# GPT_Schematic.net
KiCad netlist of a schematic drawn in Altium Designer
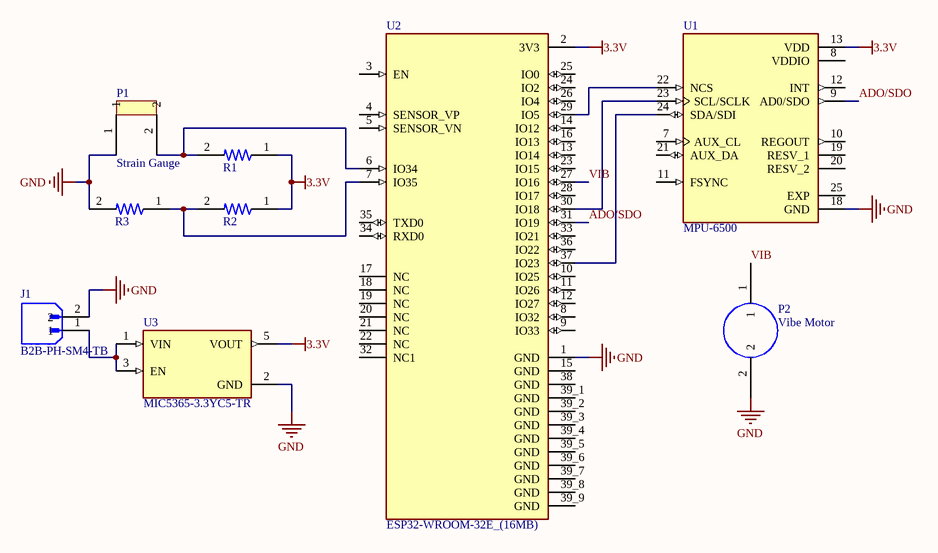
[diagram p0: GPT_Schematic.SchDoc]

(export (version "E")
  (design (tool "Eeschema 10.0.6"))
  (components
    (comp (ref "J1")
      (value "B2B-PH-SM4-TB")
      (footprint "JST_B2B-PH-SM4-TB")
      (description "Connector Header Surface Mount 2 position 0.079 (2.00mm)")
      (fields (field (name "MF") "JST"))
      (libsource (lib "B2B-PH-SM4-TB") (part "B2B-PH-SM4-TB"))
    )
    (comp (ref "P1")
      (value "Strain Gauge")
      (footprint "Strain Gauge")
      (libsource (lib "GPT_PCB") (part "Strain Gauge"))
    )
    (comp (ref "P2")
      (value "Vibe Motor")
      (footprint "Vibe Motor")
      (libsource (lib "GPT_PCB") (part "Vibe Motor"))
    )
    (comp (ref "R1")
      (value "RC0603FR-07100RL")
      (footprint "RESC1607X60N")
      (description "RES SMT 100R 1% 0603 T/R PICK#92931")
      (libsource (lib "RC0603FR-07100RL") (part "RC0603FR-07100RL"))
    )
    (comp (ref "R2")
      (value "RC0603FR-07100RL")
      (footprint "RESC1607X60N")
      (description "RES SMT 100R 1% 0603 T/R PICK#92931")
      (libsource (lib "RC0603FR-07100RL") (part "RC0603FR-07100RL"))
    )
    (comp (ref "R3")
      (value "RC0603FR-07100RL")
      (footprint "RESC1607X60N")
      (description "RES SMT 100R 1% 0603 T/R PICK#92931")
      (libsource (lib "RC0603FR-07100RL") (part "RC0603FR-07100RL"))
    )
    (comp (ref "U1")
      (value "MPU-6500")
      (footprint "QFN40P300X300X95-25N")
      (description "Accelerometer, Gyroscope, 6 Axis Sensor IÂ²C, SPI Output")
      (fields (field (name "MF") "TDK InvenSense"))
      (libsource (lib "MPU-6500") (part "MPU-6500"))
    )
    (comp (ref "U2")
      (value "ESP32-WROOM-32E_(16MB)")
      (footprint "XCVR_ESP32-WROOM-32E_(16MB)")
      (fields (field (name "MP") "ESP32-WROOM-32E (16MB)") (field (name "MF") "Espressif Systems"))
      (libsource (lib "ESP32-WROOM-32E__16MB_") (part "ESP32-WROOM-32E_(16MB)"))
    )
    (comp (ref "U3")
      (value "MIC5365-3.3YC5-TR")
      (footprint "SOT65P210X110-5N")
      (description "Linear Voltage Regulator IC 1 Output 150mA SC-70-5")
      (libsource (lib "MIC5365-3.3YC5-TR") (part "MIC5365-3.3YC5-TR"))
    )
  )
  (nets
    (net (code "1") (name "/ADO{slash}SDO") (class "Default")
      (node (ref "U1") (pin "9") (pinfunction "AD0/SDO_9") (pintype "output"))
      (node (ref "U2") (pin "31") (pinfunction "IO19_31") (pintype "bidirectional"))
    )
    (net (code "2") (name "/VIB") (class "Default")
      (node (ref "P2") (pin "1") (pinfunction "1_1") (pintype "passive"))
      (node (ref "U2") (pin "27") (pinfunction "IO16_27") (pintype "bidirectional"))
    )
    (net (code "3") (name "3.3V") (class "Default")
      (node (ref "R1") (pin "1") (pinfunction "1_1") (pintype "passive"))
      (node (ref "R2") (pin "1") (pinfunction "1_1") (pintype "passive"))
      (node (ref "U1") (pin "13") (pinfunction "VDD_13") (pintype "power_in"))
      (node (ref "U2") (pin "2") (pinfunction "3V3_2") (pintype "power_in"))
      (node (ref "U3") (pin "5") (pinfunction "VOUT_5") (pintype "output"))
    )
    (net (code "4") (name "GND") (class "Default")
      (node (ref "J1") (pin "2") (pinfunction "2_2") (pintype "passive"))
      (node (ref "P1") (pin "1") (pinfunction "1_1") (pintype "passive"))
      (node (ref "P2") (pin "2") (pinfunction "2_2") (pintype "passive"))
      (node (ref "R3") (pin "2") (pinfunction "2_2") (pintype "passive"))
      (node (ref "U1") (pin "18") (pinfunction "GND_18") (pintype "power_in"))
      (node (ref "U2") (pin "1") (pinfunction "GND_1") (pintype "power_in"))
      (node (ref "U3") (pin "2") (pinfunction "GND_2") (pintype "power_in"))
    )
    (net (code "5") (name "Net-(U1-NCS)") (class "Default")
      (node (ref "U1") (pin "22") (pinfunction "NCS_22") (pintype "input"))
      (node (ref "U2") (pin "29") (pinfunction "IO5_29") (pintype "bidirectional"))
    )
    (net (code "6") (name "Net-(U1-SCL{slash}SCLK)") (class "Default")
      (node (ref "U1") (pin "23") (pinfunction "SCL/SCLK_23") (pintype "input"))
      (node (ref "U2") (pin "30") (pinfunction "IO18_30") (pintype "bidirectional"))
    )
    (net (code "7") (name "Net-(U1-SDA{slash}SDI)") (class "Default")
      (node (ref "U1") (pin "24") (pinfunction "SDA/SDI_24") (pintype "bidirectional"))
      (node (ref "U2") (pin "37") (pinfunction "IO23_37") (pintype "bidirectional"))
    )
    (net (code "8") (name "Net-(U2-IO34)") (class "Default")
      (node (ref "P1") (pin "2") (pinfunction "2_2") (pintype "passive"))
      (node (ref "R1") (pin "2") (pinfunction "2_2") (pintype "passive"))
      (node (ref "U2") (pin "6") (pinfunction "IO34_6") (pintype "input"))
    )
    (net (code "9") (name "Net-(U2-IO35)") (class "Default")
      (node (ref "R2") (pin "2") (pinfunction "2_2") (pintype "passive"))
      (node (ref "R3") (pin "1") (pinfunction "1_1") (pintype "passive"))
      (node (ref "U2") (pin "7") (pinfunction "IO35_7") (pintype "input"))
    )
    (net (code "10") (name "Net-(U3-EN)") (class "Default")
      (node (ref "J1") (pin "1") (pinfunction "1_1") (pintype "passive"))
      (node (ref "U3") (pin "1") (pinfunction "VIN_1") (pintype "input"))
      (node (ref "U3") (pin "3") (pinfunction "EN_3") (pintype "input"))
    )
    (net (code "11") (name "unconnected-(U1-AUX_CL-Pad7)") (class "Default")
      (node (ref "U1") (pin "7") (pinfunction "AUX_CL_7") (pintype "input"))
    )
    (net (code "12") (name "unconnected-(U1-AUX_DA-Pad21)") (class "Default")
      (node (ref "U1") (pin "21") (pinfunction "AUX_DA_21") (pintype "bidirectional"))
    )
    (net (code "13") (name "unconnected-(U1-EXP-Pad25)") (class "Default")
      (node (ref "U1") (pin "25") (pinfunction "EXP_25") (pintype "passive"))
    )
    (net (code "14") (name "unconnected-(U1-FSYNC-Pad11)") (class "Default")
      (node (ref "U1") (pin "11") (pinfunction "FSYNC_11") (pintype "input"))
    )
    (net (code "15") (name "unconnected-(U1-INT-Pad12)") (class "Default")
      (node (ref "U1") (pin "12") (pinfunction "INT_12") (pintype "output"))
    )
    (net (code "16") (name "unconnected-(U1-REGOUT-Pad10)") (class "Default")
      (node (ref "U1") (pin "10") (pinfunction "REGOUT_10") (pintype "output"))
    )
    (net (code "17") (name "unconnected-(U1-RESV_1-Pad19)") (class "Default")
      (node (ref "U1") (pin "19") (pinfunction "RESV_1_19") (pintype "passive"))
    )
    (net (code "18") (name "unconnected-(U1-RESV_2-Pad20)") (class "Default")
      (node (ref "U1") (pin "20") (pinfunction "RESV_2_20") (pintype "passive"))
    )
    (net (code "19") (name "unconnected-(U1-VDDIO-Pad8)") (class "Default")
      (node (ref "U1") (pin "8") (pinfunction "VDDIO_8") (pintype "power_in"))
    )
    (net (code "20") (name "unconnected-(U2-EN-Pad3)") (class "Default")
      (node (ref "U2") (pin "3") (pinfunction "EN_3") (pintype "input"))
    )
    (net (code "21") (name "unconnected-(U2-GND-Pad15)") (class "Default")
      (node (ref "U2") (pin "15") (pinfunction "GND_15") (pintype "power_in"))
    )
    (net (code "22") (name "unconnected-(U2-GND-Pad38)") (class "Default")
      (node (ref "U2") (pin "38") (pinfunction "GND_38") (pintype "power_in"))
    )
    (net (code "23") (name "unconnected-(U2-GND-Pad39_1)") (class "Default")
      (node (ref "U2") (pin "39_1") (pinfunction "GND_39_1") (pintype "power_in"))
    )
    (net (code "24") (name "unconnected-(U2-GND-Pad39_2)") (class "Default")
      (node (ref "U2") (pin "39_2") (pinfunction "GND_39_2") (pintype "power_in"))
    )
    (net (code "25") (name "unconnected-(U2-GND-Pad39_3)") (class "Default")
      (node (ref "U2") (pin "39_3") (pinfunction "GND_39_3") (pintype "power_in"))
    )
    (net (code "26") (name "unconnected-(U2-GND-Pad39_4)") (class "Default")
      (node (ref "U2") (pin "39_4") (pinfunction "GND_39_4") (pintype "power_in"))
    )
    (net (code "27") (name "unconnected-(U2-GND-Pad39_5)") (class "Default")
      (node (ref "U2") (pin "39_5") (pinfunction "GND_39_5") (pintype "power_in"))
    )
    (net (code "28") (name "unconnected-(U2-GND-Pad39_6)") (class "Default")
      (node (ref "U2") (pin "39_6") (pinfunction "GND_39_6") (pintype "power_in"))
    )
    (net (code "29") (name "unconnected-(U2-GND-Pad39_7)") (class "Default")
      (node (ref "U2") (pin "39_7") (pinfunction "GND_39_7") (pintype "power_in"))
    )
    (net (code "30") (name "unconnected-(U2-GND-Pad39_8)") (class "Default")
      (node (ref "U2") (pin "39_8") (pinfunction "GND_39_8") (pintype "power_in"))
    )
    (net (code "31") (name "unconnected-(U2-GND-Pad39_9)") (class "Default")
      (node (ref "U2") (pin "39_9") (pinfunction "GND_39_9") (pintype "power_in"))
    )
    (net (code "32") (name "unconnected-(U2-IO0-Pad25)") (class "Default")
      (node (ref "U2") (pin "25") (pinfunction "IO0_25") (pintype "bidirectional"))
    )
    (net (code "33") (name "unconnected-(U2-IO2-Pad24)") (class "Default")
      (node (ref "U2") (pin "24") (pinfunction "IO2_24") (pintype "bidirectional"))
    )
    (net (code "34") (name "unconnected-(U2-IO4-Pad26)") (class "Default")
      (node (ref "U2") (pin "26") (pinfunction "IO4_26") (pintype "bidirectional"))
    )
    (net (code "35") (name "unconnected-(U2-IO12-Pad14)") (class "Default")
      (node (ref "U2") (pin "14") (pinfunction "IO12_14") (pintype "bidirectional"))
    )
    (net (code "36") (name "unconnected-(U2-IO13-Pad16)") (class "Default")
      (node (ref "U2") (pin "16") (pinfunction "IO13_16") (pintype "bidirectional"))
    )
    (net (code "37") (name "unconnected-(U2-IO14-Pad13)") (class "Default")
      (node (ref "U2") (pin "13") (pinfunction "IO14_13") (pintype "bidirectional"))
    )
    (net (code "38") (name "unconnected-(U2-IO15-Pad23)") (class "Default")
      (node (ref "U2") (pin "23") (pinfunction "IO15_23") (pintype "bidirectional"))
    )
    (net (code "39") (name "unconnected-(U2-IO17-Pad28)") (class "Default")
      (node (ref "U2") (pin "28") (pinfunction "IO17_28") (pintype "bidirectional"))
    )
    (net (code "40") (name "unconnected-(U2-IO21-Pad33)") (class "Default")
      (node (ref "U2") (pin "33") (pinfunction "IO21_33") (pintype "bidirectional"))
    )
    (net (code "41") (name "unconnected-(U2-IO22-Pad36)") (class "Default")
      (node (ref "U2") (pin "36") (pinfunction "IO22_36") (pintype "bidirectional"))
    )
    (net (code "42") (name "unconnected-(U2-IO25-Pad10)") (class "Default")
      (node (ref "U2") (pin "10") (pinfunction "IO25_10") (pintype "bidirectional"))
    )
    (net (code "43") (name "unconnected-(U2-IO26-Pad11)") (class "Default")
      (node (ref "U2") (pin "11") (pinfunction "IO26_11") (pintype "bidirectional"))
    )
    (net (code "44") (name "unconnected-(U2-IO27-Pad12)") (class "Default")
      (node (ref "U2") (pin "12") (pinfunction "IO27_12") (pintype "bidirectional"))
    )
    (net (code "45") (name "unconnected-(U2-IO32-Pad8)") (class "Default")
      (node (ref "U2") (pin "8") (pinfunction "IO32_8") (pintype "bidirectional"))
    )
    (net (code "46") (name "unconnected-(U2-IO33-Pad9)") (class "Default")
      (node (ref "U2") (pin "9") (pinfunction "IO33_9") (pintype "bidirectional"))
    )
    (net (code "47") (name "unconnected-(U2-NC-Pad17)") (class "Default")
      (node (ref "U2") (pin "17") (pinfunction "NC_17") (pintype "passive"))
    )
    (net (code "48") (name "unconnected-(U2-NC-Pad18)") (class "Default")
      (node (ref "U2") (pin "18") (pinfunction "NC_18") (pintype "passive"))
    )
    (net (code "49") (name "unconnected-(U2-NC-Pad19)") (class "Default")
      (node (ref "U2") (pin "19") (pinfunction "NC_19") (pintype "passive"))
    )
    (net (code "50") (name "unconnected-(U2-NC-Pad20)") (class "Default")
      (node (ref "U2") (pin "20") (pinfunction "NC_20") (pintype "passive"))
    )
    (net (code "51") (name "unconnected-(U2-NC-Pad21)") (class "Default")
      (node (ref "U2") (pin "21") (pinfunction "NC_21") (pintype "passive"))
    )
    (net (code "52") (name "unconnected-(U2-NC-Pad22)") (class "Default")
      (node (ref "U2") (pin "22") (pinfunction "NC_22") (pintype "passive"))
    )
    (net (code "53") (name "unconnected-(U2-NC1-Pad32)") (class "Default")
      (node (ref "U2") (pin "32") (pinfunction "NC1_32") (pintype "passive"))
    )
    (net (code "54") (name "unconnected-(U2-RXD0-Pad34)") (class "Default")
      (node (ref "U2") (pin "34") (pinfunction "RXD0_34") (pintype "bidirectional"))
    )
    (net (code "55") (name "unconnected-(U2-SENSOR_VN-Pad5)") (class "Default")
      (node (ref "U2") (pin "5") (pinfunction "SENSOR_VN_5") (pintype "input"))
    )
    (net (code "56") (name "unconnected-(U2-SENSOR_VP-Pad4)") (class "Default")
      (node (ref "U2") (pin "4") (pinfunction "SENSOR_VP_4") (pintype "input"))
    )
    (net (code "57") (name "unconnected-(U2-TXD0-Pad35)") (class "Default")
      (node (ref "U2") (pin "35") (pinfunction "TXD0_35") (pintype "bidirectional"))
    )
  )
)
